# Overgang.net
KiCad netlist of a schematic drawn in EAGLE
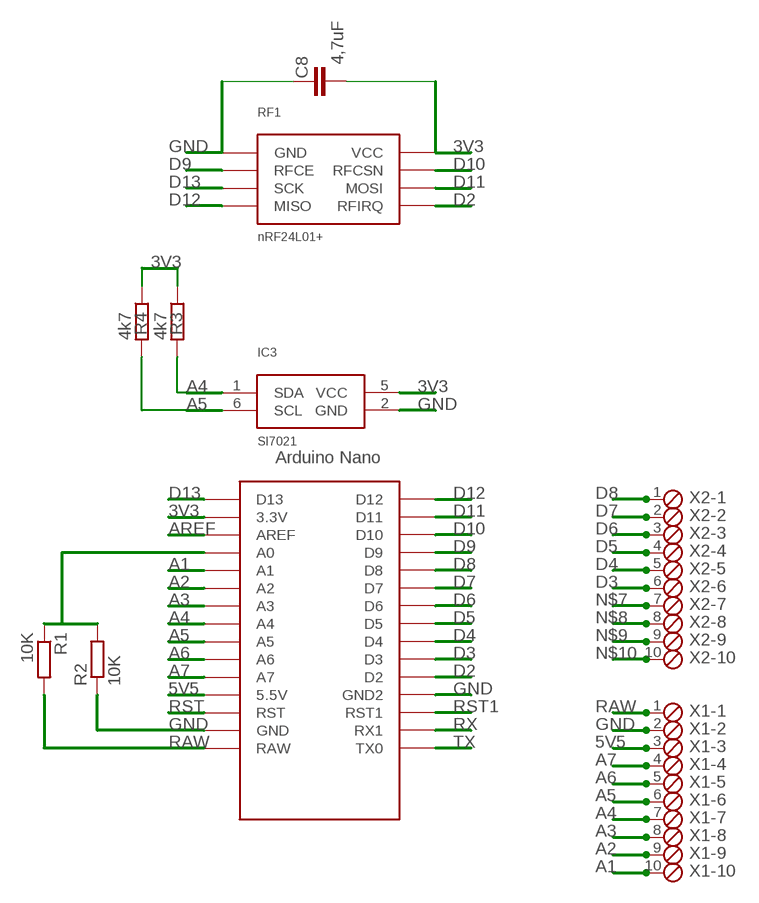
[diagram p0: schematic, sheet 1]

(export (version "E")
  (design (tool "Eeschema 10.0.6"))
  (components
    (comp (ref "C8")
      (value "4,7uF")
      (footprint "eagle-import:C1206K")
      (libsource (lib "eagle-import") (part "C-EUC1206K"))
    )
    (comp (ref "IC3")
      (value "SI7021")
      (footprint "eagle-import:DFN6")
      (libsource (lib "eagle-import") (part "SI7021"))
    )
    (comp (ref "R1")
      (value "10K")
      (footprint "eagle-import:R0805")
      (libsource (lib "eagle-import") (part "R-EU_R0805"))
    )
    (comp (ref "R2")
      (value "10K")
      (footprint "eagle-import:R0805")
      (libsource (lib "eagle-import") (part "R-EU_R0805"))
    )
    (comp (ref "R3")
      (value "4k7")
      (footprint "eagle-import:R0805")
      (libsource (lib "eagle-import") (part "R-EU_R0805"))
    )
    (comp (ref "R4")
      (value "4k7")
      (footprint "eagle-import:R0805")
      (libsource (lib "eagle-import") (part "R-EU_R0805"))
    )
    (comp (ref "RF1")
      (value "nRF24L01+")
      (footprint "eagle-import:2X4-2.54MM")
      (libsource (lib "eagle-import") (part "NRF24L01"))
    )
    (comp (ref "U$1")
      (value "NANO")
      (footprint "eagle-import:NANO")
      (libsource (lib "eagle-import") (part "NANO"))
    )
    (comp (ref "X1")
      (value "MPT10")
      (footprint "eagle-import:10POL254")
      (libsource (lib "eagle-import") (part "MPT10"))
    )
    (comp (ref "X2")
      (value "MPT10")
      (footprint "eagle-import:10POL254")
      (libsource (lib "eagle-import") (part "MPT10"))
    )
  )
  (nets
    (net (code "1") (name "/3V3") (class "Default")
      (node (ref "C8") (pin "1") (pinfunction "1_1") (pintype "passive"))
      (node (ref "IC3") (pin "5") (pinfunction "VCC_5") (pintype "bidirectional"))
      (node (ref "R3") (pin "1") (pinfunction "1_1") (pintype "passive"))
      (node (ref "R4") (pin "1") (pinfunction "1_1") (pintype "passive"))
      (node (ref "RF1") (pin "P$2") (pinfunction "VCC_P$2") (pintype "power_in"))
      (node (ref "U$1") (pin "3.3V") (pinfunction "3.3V_3.3V") (pintype "bidirectional"))
    )
    (net (code "2") (name "/5V5") (class "Default")
      (node (ref "U$1") (pin "5V") (pinfunction "5.5V_5V") (pintype "bidirectional"))
      (node (ref "X1") (pin "3") (pinfunction "1_3") (pintype "passive"))
    )
    (net (code "3") (name "/A1") (class "Default")
      (node (ref "U$1") (pin "A1") (pinfunction "A1_A1") (pintype "bidirectional"))
      (node (ref "X1") (pin "10") (pinfunction "1_10") (pintype "passive"))
    )
    (net (code "4") (name "/A2") (class "Default")
      (node (ref "U$1") (pin "A2") (pinfunction "A2_A2") (pintype "bidirectional"))
      (node (ref "X1") (pin "9") (pinfunction "1_9") (pintype "passive"))
    )
    (net (code "5") (name "/A3") (class "Default")
      (node (ref "U$1") (pin "A3") (pinfunction "A3_A3") (pintype "bidirectional"))
      (node (ref "X1") (pin "8") (pinfunction "1_8") (pintype "passive"))
    )
    (net (code "6") (name "/A4") (class "Default")
      (node (ref "IC3") (pin "1") (pinfunction "SDA_1") (pintype "bidirectional"))
      (node (ref "R3") (pin "2") (pinfunction "2_2") (pintype "passive"))
      (node (ref "U$1") (pin "A4") (pinfunction "A4_A4") (pintype "bidirectional"))
      (node (ref "X1") (pin "7") (pinfunction "1_7") (pintype "passive"))
    )
    (net (code "7") (name "/A5") (class "Default")
      (node (ref "IC3") (pin "6") (pinfunction "SCL_6") (pintype "bidirectional"))
      (node (ref "R4") (pin "2") (pinfunction "2_2") (pintype "passive"))
      (node (ref "U$1") (pin "A5") (pinfunction "A5_A5") (pintype "bidirectional"))
      (node (ref "X1") (pin "6") (pinfunction "1_6") (pintype "passive"))
    )
    (net (code "8") (name "/A6") (class "Default")
      (node (ref "U$1") (pin "A6") (pinfunction "A6_A6") (pintype "bidirectional"))
      (node (ref "X1") (pin "5") (pinfunction "1_5") (pintype "passive"))
    )
    (net (code "9") (name "/A7") (class "Default")
      (node (ref "U$1") (pin "A7") (pinfunction "A7_A7") (pintype "bidirectional"))
      (node (ref "X1") (pin "4") (pinfunction "1_4") (pintype "passive"))
    )
    (net (code "10") (name "/AREF") (class "Default")
      (node (ref "U$1") (pin "AREF") (pinfunction "AREF_AREF") (pintype "bidirectional"))
    )
    (net (code "11") (name "/D2") (class "Default")
      (node (ref "RF1") (pin "P$8") (pinfunction "RFIRQ_P$8") (pintype "output"))
      (node (ref "U$1") (pin "D2") (pinfunction "D2_D2") (pintype "bidirectional"))
    )
    (net (code "12") (name "/D3") (class "Default")
      (node (ref "U$1") (pin "D3") (pinfunction "D3_D3") (pintype "bidirectional"))
      (node (ref "X2") (pin "6") (pinfunction "1_6") (pintype "passive"))
    )
    (net (code "13") (name "/D4") (class "Default")
      (node (ref "U$1") (pin "D4") (pinfunction "D4_D4") (pintype "bidirectional"))
      (node (ref "X2") (pin "5") (pinfunction "1_5") (pintype "passive"))
    )
    (net (code "14") (name "/D5") (class "Default")
      (node (ref "U$1") (pin "D5") (pinfunction "D5_D5") (pintype "bidirectional"))
      (node (ref "X2") (pin "4") (pinfunction "1_4") (pintype "passive"))
    )
    (net (code "15") (name "/D6") (class "Default")
      (node (ref "U$1") (pin "D6") (pinfunction "D6_D6") (pintype "bidirectional"))
      (node (ref "X2") (pin "3") (pinfunction "1_3") (pintype "passive"))
    )
    (net (code "16") (name "/D7") (class "Default")
      (node (ref "U$1") (pin "D7") (pinfunction "D7_D7") (pintype "bidirectional"))
      (node (ref "X2") (pin "2") (pinfunction "1_2") (pintype "passive"))
    )
    (net (code "17") (name "/D8") (class "Default")
      (node (ref "U$1") (pin "D8") (pinfunction "D8_D8") (pintype "bidirectional"))
      (node (ref "X2") (pin "1") (pinfunction "1_1") (pintype "passive"))
    )
    (net (code "18") (name "/D9") (class "Default")
      (node (ref "RF1") (pin "P$3") (pinfunction "RFCE_P$3") (pintype "input"))
      (node (ref "U$1") (pin "D9") (pinfunction "D9_D9") (pintype "bidirectional"))
    )
    (net (code "19") (name "/D10") (class "Default")
      (node (ref "RF1") (pin "P$4") (pinfunction "RFCSN_P$4") (pintype "bidirectional"))
      (node (ref "U$1") (pin "D10") (pinfunction "D10_D10") (pintype "bidirectional"))
    )
    (net (code "20") (name "/D11") (class "Default")
      (node (ref "RF1") (pin "P$6") (pinfunction "MOSI_P$6") (pintype "bidirectional"))
      (node (ref "U$1") (pin "D11") (pinfunction "D11_D11") (pintype "bidirectional"))
    )
    (net (code "21") (name "/D12") (class "Default")
      (node (ref "RF1") (pin "P$7") (pinfunction "MISO_P$7") (pintype "bidirectional"))
      (node (ref "U$1") (pin "D12") (pinfunction "D12_D12") (pintype "bidirectional"))
    )
    (net (code "22") (name "/D13") (class "Default")
      (node (ref "RF1") (pin "P$5") (pinfunction "SCK_P$5") (pintype "input"))
      (node (ref "U$1") (pin "D13") (pinfunction "D13_D13") (pintype "bidirectional"))
    )
    (net (code "23") (name "/GND") (class "Default")
      (node (ref "C8") (pin "2") (pinfunction "2_2") (pintype "passive"))
      (node (ref "IC3") (pin "2") (pinfunction "GND_2") (pintype "bidirectional"))
      (node (ref "R2") (pin "1") (pinfunction "1_1") (pintype "passive"))
      (node (ref "RF1") (pin "P$1") (pinfunction "GND_P$1") (pintype "power_in"))
      (node (ref "U$1") (pin "GND") (pinfunction "GND_GND") (pintype "bidirectional"))
      (node (ref "U$1") (pin "GND1") (pinfunction "GND2_GND1") (pintype "bidirectional"))
      (node (ref "X1") (pin "2") (pinfunction "1_2") (pintype "passive"))
    )
    (net (code "24") (name "/N$7") (class "Default")
      (node (ref "X2") (pin "7") (pinfunction "1_7") (pintype "passive"))
    )
    (net (code "25") (name "/N$8") (class "Default")
      (node (ref "X2") (pin "8") (pinfunction "1_8") (pintype "passive"))
    )
    (net (code "26") (name "/N$9") (class "Default")
      (node (ref "X2") (pin "9") (pinfunction "1_9") (pintype "passive"))
    )
    (net (code "27") (name "/N$10") (class "Default")
      (node (ref "X2") (pin "10") (pinfunction "1_10") (pintype "passive"))
    )
    (net (code "28") (name "/RAW") (class "Default")
      (node (ref "R1") (pin "2") (pinfunction "2_2") (pintype "passive"))
      (node (ref "U$1") (pin "RAW") (pinfunction "RAW_RAW") (pintype "bidirectional"))
      (node (ref "X1") (pin "1") (pinfunction "1_1") (pintype "passive"))
    )
    (net (code "29") (name "/RST") (class "Default")
      (node (ref "U$1") (pin "RST") (pinfunction "RST_RST") (pintype "bidirectional"))
    )
    (net (code "30") (name "/RST1") (class "Default")
      (node (ref "U$1") (pin "RST1") (pinfunction "RST1_RST1") (pintype "bidirectional"))
    )
    (net (code "31") (name "/RX") (class "Default")
      (node (ref "U$1") (pin "RX1") (pinfunction "RX1_RX1") (pintype "bidirectional"))
    )
    (net (code "32") (name "/TX") (class "Default")
      (node (ref "U$1") (pin "TX0") (pinfunction "TX0_TX0") (pintype "bidirectional"))
    )
    (net (code "33") (name "Net-(R1-Pad1)") (class "Default")
      (node (ref "R1") (pin "1") (pinfunction "1_1") (pintype "passive"))
      (node (ref "R2") (pin "2") (pinfunction "2_2") (pintype "passive"))
      (node (ref "U$1") (pin "A0") (pinfunction "A0_A0") (pintype "bidirectional"))
    )
    (net (code "34") (name "unconnected-(U$1-PadICSP1)") (class "Default")
      (node (ref "U$1") (pin "ICSP1") (pinfunction "ICSP1_ICSP1") (pintype "bidirectional"))
    )
    (net (code "35") (name "unconnected-(U$1-PadICSP2)") (class "Default")
      (node (ref "U$1") (pin "ICSP2") (pinfunction "ICSP2_ICSP2") (pintype "bidirectional"))
    )
    (net (code "36") (name "unconnected-(U$1-PadICSP3)") (class "Default")
      (node (ref "U$1") (pin "ICSP3") (pinfunction "ICSP3_ICSP3") (pintype "bidirectional"))
    )
    (net (code "37") (name "unconnected-(U$1-PadICSP4)") (class "Default")
      (node (ref "U$1") (pin "ICSP4") (pinfunction "ICSP4_ICSP4") (pintype "bidirectional"))
    )
    (net (code "38") (name "unconnected-(U$1-PadICSP5)") (class "Default")
      (node (ref "U$1") (pin "ICSP5") (pinfunction "ICSP5_ICSP5") (pintype "bidirectional"))
    )
    (net (code "39") (name "unconnected-(U$1-PadICSP6)") (class "Default")
      (node (ref "U$1") (pin "ICSP6") (pinfunction "ICSP6_ICSP6") (pintype "bidirectional"))
    )
  )
)
